# design.net
KiCad netlist of a schematic drawn in EasyEDA
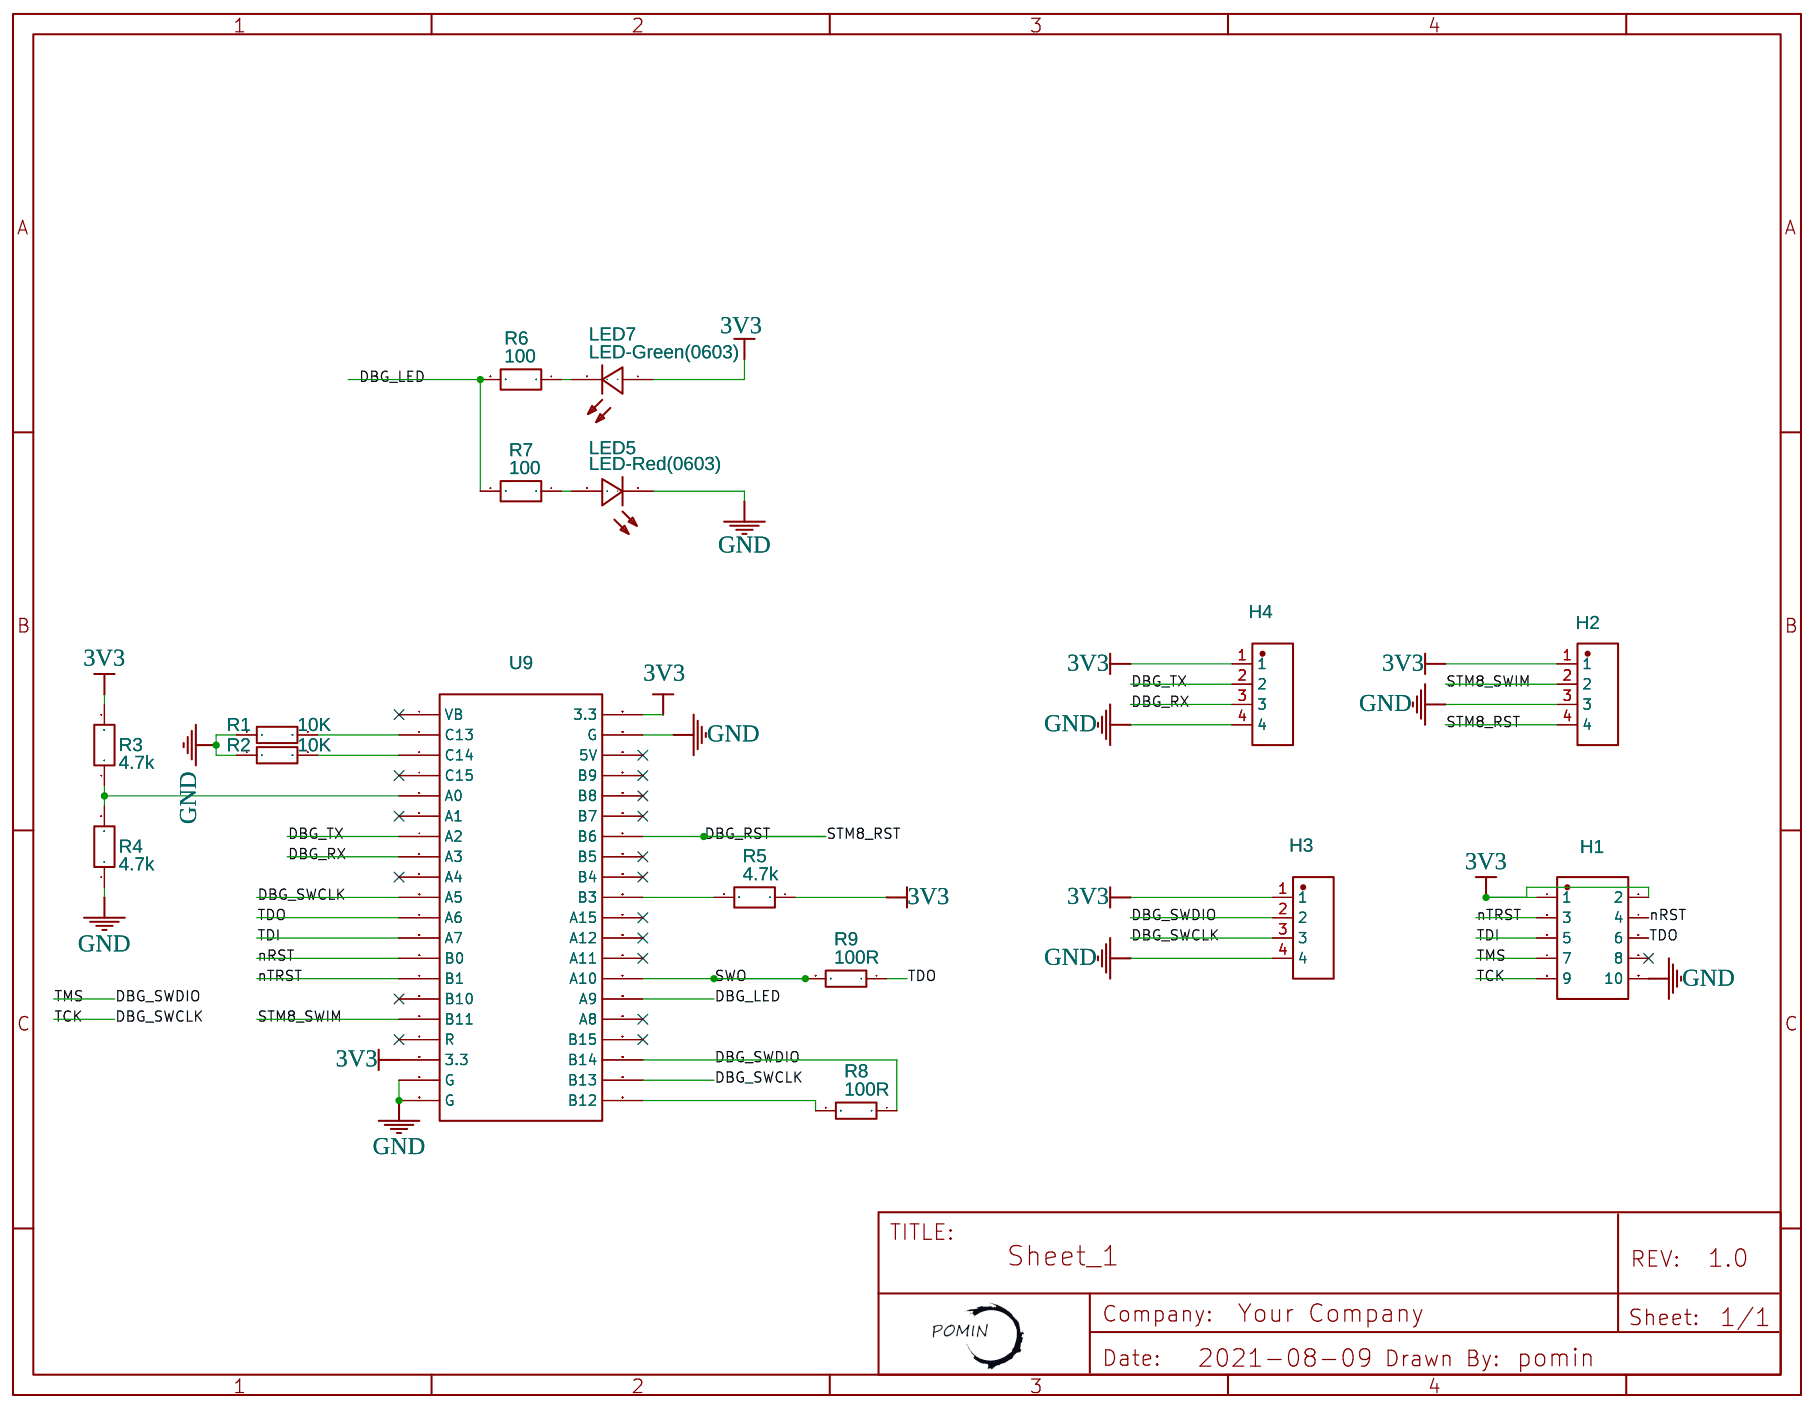
[diagram p0: schematic sheet]

(export (version "E")
  (design (tool "Eeschema 10.0.6"))
  (components
    (comp (ref "H1")
      (value "Female header2.54mm2*5p Straight")
      (fields (field (name "BOM_Supplier Part") "C30419"))
      (libsource (lib "") (part "Female header2.54mm2*5p Straight"))
    )
    (comp (ref "H2")
      (value "2.54-1*4P母")
      (fields (field (name "BOM_Supplier Part") "C2718488"))
      (libsource (lib "") (part "2.54-1*4P母"))
    )
    (comp (ref "H3")
      (value "2.54-1*4P母")
      (fields (field (name "BOM_Supplier Part") "C2718488"))
      (libsource (lib "") (part "2.54-1*4P母"))
    )
    (comp (ref "H4")
      (value "2.54-1*4P母")
      (fields (field (name "BOM_Supplier Part") "C2718488"))
      (libsource (lib "") (part "2.54-1*4P母"))
    )
    (comp (ref "LED5")
      (value "LED-Red(0603)")
      (fields (field (name "BOM_Manufacturer Part") "KT-0603R") (field (name "BOM_Supplier Part") "C2286"))
      (libsource (lib "") (part "Unknown_535_-405"))
    )
    (comp (ref "LED7")
      (value "LED-Green(0603)")
      (fields
        (field (name "BOM_Manufacturer Part") "FC-DA1608UGK-520D10")
        (field (name "BOM_Supplier Part") "C84267")
      )
      (libsource (lib "") (part "Unknown_535_-460"))
    )
    (comp (ref "R1")
      (value "10K")
      (fields
        (field (name "BOM_Manufacturer Part") "AC0603FR-0710KL")
        (field (name "BOM_Supplier Part") "C116677")
      )
      (libsource (lib "") (part "RC0603DR-0710KL"))
    )
    (comp (ref "R2")
      (value "10K")
      (fields
        (field (name "BOM_Manufacturer Part") "AC0603FR-0710KL")
        (field (name "BOM_Supplier Part") "C116677")
      )
      (libsource (lib "") (part "RC0603DR-0710KL"))
    )
    (comp (ref "R3")
      (value "4.7k")
      (fields
        (field (name "BOM_Manufacturer Part") "AC0603FR-074K7L")
        (field (name "BOM_Supplier Part") "C116697")
      )
      (libsource (lib "") (part "Res_0603(1/10W)_EU"))
    )
    (comp (ref "R4")
      (value "4.7k")
      (fields
        (field (name "BOM_Manufacturer Part") "AC0603FR-074K7L")
        (field (name "BOM_Supplier Part") "C116697")
      )
      (libsource (lib "") (part "Res_0603(1/10W)_EU"))
    )
    (comp (ref "R5")
      (value "4.7k")
      (fields
        (field (name "BOM_Manufacturer Part") "AC0603FR-074K7L")
        (field (name "BOM_Supplier Part") "C116697")
      )
      (libsource (lib "") (part "Res_0603(1/10W)_EU_1"))
    )
    (comp (ref "R6")
      (value "100")
      (fields (field (name "BOM_Manufacturer Part") "?"))
      (libsource (lib "") (part "Res_0603(1/10W)_EU_1"))
    )
    (comp (ref "R7")
      (value "100")
      (fields (field (name "BOM_Manufacturer Part") "?"))
      (libsource (lib "") (part "Res_0603(1/10W)_EU_1"))
    )
    (comp (ref "R8")
      (value "100R")
      (fields
        (field (name "BOM_Manufacturer Part") "RC0603FR-07100RL")
        (field (name "BOM_Supplier Part") "C105588")
      )
      (libsource (lib "") (part "AC0603JR-07100RL"))
    )
    (comp (ref "R9")
      (value "100R")
      (fields
        (field (name "BOM_Manufacturer Part") "RC0603FR-07100RL")
        (field (name "BOM_Supplier Part") "C105588")
      )
      (libsource (lib "") (part "AC0603JR-07100RL"))
    )
    (comp (ref "U9") (value "STM32F103C8T6核心板") (libsource (lib "") (part "STM32F103C8T6核心板")))
  )
  (nets
    (net (code "1") (name "/DBG_LED") (class "Default")
      (node (ref "R6") (pin "2") (pinfunction "2_2") (pintype "unspecified"))
      (node (ref "R7") (pin "2") (pinfunction "2_2") (pintype "unspecified"))
      (node (ref "U9") (pin "35") (pinfunction "A9_35") (pintype "unspecified"))
    )
    (net (code "2") (name "/DBG_RST") (class "Default")
      (node (ref "H2") (pin "4") (pinfunction "4_4") (pintype "unspecified"))
      (node (ref "U9") (pin "27") (pinfunction "B6_27") (pintype "unspecified"))
    )
    (net (code "3") (name "/DBG_RX") (class "Default")
      (node (ref "H4") (pin "3") (pinfunction "3_3") (pintype "unspecified"))
      (node (ref "U9") (pin "8") (pinfunction "A3_8") (pintype "unspecified"))
    )
    (net (code "4") (name "/DBG_SWCLK") (class "Default")
      (node (ref "H1") (pin "9") (pinfunction "9_9") (pintype "unspecified"))
      (node (ref "H3") (pin "3") (pinfunction "3_3") (pintype "unspecified"))
      (node (ref "U9") (pin "10") (pinfunction "A5_10") (pintype "unspecified"))
      (node (ref "U9") (pin "39") (pinfunction "B13_39") (pintype "unspecified"))
    )
    (net (code "5") (name "/DBG_SWDIO") (class "Default")
      (node (ref "H1") (pin "7") (pinfunction "7_7") (pintype "unspecified"))
      (node (ref "H3") (pin "2") (pinfunction "2_2") (pintype "unspecified"))
      (node (ref "R8") (pin "1") (pinfunction "1_1") (pintype "unspecified"))
      (node (ref "U9") (pin "38") (pinfunction "B14_38") (pintype "unspecified"))
    )
    (net (code "6") (name "/DBG_TX") (class "Default")
      (node (ref "H4") (pin "2") (pinfunction "2_2") (pintype "unspecified"))
      (node (ref "U9") (pin "7") (pinfunction "A2_7") (pintype "unspecified"))
    )
    (net (code "7") (name "/STM8_SWIM") (class "Default")
      (node (ref "H2") (pin "2") (pinfunction "2_2") (pintype "unspecified"))
      (node (ref "U9") (pin "16") (pinfunction "B11_16") (pintype "unspecified"))
    )
    (net (code "8") (name "/SWO") (class "Default")
      (node (ref "R9") (pin "2") (pinfunction "2_2") (pintype "unspecified"))
      (node (ref "U9") (pin "34") (pinfunction "A10_34") (pintype "unspecified"))
    )
    (net (code "9") (name "/TDI") (class "Default")
      (node (ref "H1") (pin "5") (pinfunction "5_5") (pintype "unspecified"))
      (node (ref "U9") (pin "12") (pinfunction "A7_12") (pintype "unspecified"))
    )
    (net (code "10") (name "/TDO") (class "Default")
      (node (ref "H1") (pin "6") (pinfunction "6_6") (pintype "unspecified"))
      (node (ref "R9") (pin "1") (pinfunction "1_1") (pintype "unspecified"))
      (node (ref "U9") (pin "11") (pinfunction "A6_11") (pintype "unspecified"))
    )
    (net (code "11") (name "/nRST") (class "Default")
      (node (ref "H1") (pin "4") (pinfunction "4_4") (pintype "unspecified"))
      (node (ref "U9") (pin "13") (pinfunction "B0_13") (pintype "unspecified"))
    )
    (net (code "12") (name "/nTRST") (class "Default")
      (node (ref "H1") (pin "3") (pinfunction "3_3") (pintype "unspecified"))
      (node (ref "U9") (pin "14") (pinfunction "B1_14") (pintype "unspecified"))
    )
    (net (code "13") (name "3V3") (class "Default")
      (node (ref "H1") (pin "1") (pinfunction "1_1") (pintype "unspecified"))
      (node (ref "H1") (pin "2") (pinfunction "2_2") (pintype "unspecified"))
      (node (ref "H2") (pin "1") (pinfunction "1_1") (pintype "unspecified"))
      (node (ref "H3") (pin "1") (pinfunction "1_1") (pintype "unspecified"))
      (node (ref "H4") (pin "1") (pinfunction "1_1") (pintype "unspecified"))
      (node (ref "LED7") (pin "1") (pinfunction "+_1") (pintype "unspecified"))
      (node (ref "R3") (pin "2") (pinfunction "2_2") (pintype "unspecified"))
      (node (ref "R5") (pin "1") (pinfunction "1_1") (pintype "unspecified"))
      (node (ref "U9") (pin "18") (pinfunction "3.3_18") (pintype "unspecified"))
      (node (ref "U9") (pin "21") (pinfunction "3.3_21") (pintype "unspecified"))
    )
    (net (code "14") (name "GND") (class "Default")
      (node (ref "H1") (pin "10") (pinfunction "10_10") (pintype "unspecified"))
      (node (ref "H2") (pin "3") (pinfunction "3_3") (pintype "unspecified"))
      (node (ref "H3") (pin "4") (pinfunction "4_4") (pintype "unspecified"))
      (node (ref "H4") (pin "4") (pinfunction "4_4") (pintype "unspecified"))
      (node (ref "LED5") (pin "2") (pinfunction "-_2") (pintype "unspecified"))
      (node (ref "R1") (pin "1") (pinfunction "1_1") (pintype "input"))
      (node (ref "R2") (pin "1") (pinfunction "1_1") (pintype "input"))
      (node (ref "R4") (pin "1") (pinfunction "1_1") (pintype "unspecified"))
      (node (ref "U9") (pin "19") (pinfunction "G_19") (pintype "unspecified"))
      (node (ref "U9") (pin "20") (pinfunction "G_20") (pintype "unspecified"))
      (node (ref "U9") (pin "22") (pinfunction "G_22") (pintype "unspecified"))
    )
    (net (code "15") (name "Net-(LED5-+)") (class "Default")
      (node (ref "LED5") (pin "1") (pinfunction "+_1") (pintype "unspecified"))
      (node (ref "R7") (pin "1") (pinfunction "1_1") (pintype "unspecified"))
    )
    (net (code "16") (name "Net-(LED7--)") (class "Default")
      (node (ref "LED7") (pin "2") (pinfunction "-_2") (pintype "unspecified"))
      (node (ref "R6") (pin "1") (pinfunction "1_1") (pintype "unspecified"))
    )
    (net (code "17") (name "Net-(U9-A0)") (class "Default")
      (node (ref "R3") (pin "1") (pinfunction "1_1") (pintype "unspecified"))
      (node (ref "R4") (pin "2") (pinfunction "2_2") (pintype "unspecified"))
      (node (ref "U9") (pin "5") (pinfunction "A0_5") (pintype "unspecified"))
    )
    (net (code "18") (name "Net-(U9-B3)") (class "Default")
      (node (ref "R5") (pin "2") (pinfunction "2_2") (pintype "unspecified"))
      (node (ref "U9") (pin "30") (pinfunction "B3_30") (pintype "unspecified"))
    )
    (net (code "19") (name "Net-(U9-B12)") (class "Default")
      (node (ref "R8") (pin "2") (pinfunction "2_2") (pintype "unspecified"))
      (node (ref "U9") (pin "40") (pinfunction "B12_40") (pintype "unspecified"))
    )
    (net (code "20") (name "Net-(U9-C13)") (class "Default")
      (node (ref "R1") (pin "2") (pinfunction "2_2") (pintype "input"))
      (node (ref "U9") (pin "2") (pinfunction "C13_2") (pintype "unspecified"))
    )
    (net (code "21") (name "Net-(U9-C14)") (class "Default")
      (node (ref "R2") (pin "2") (pinfunction "2_2") (pintype "input"))
      (node (ref "U9") (pin "3") (pinfunction "C14_3") (pintype "unspecified"))
    )
    (net (code "22") (name "unconnected-(H1-Pad8)") (class "Default")
      (node (ref "H1") (pin "8") (pinfunction "8_8") (pintype "unspecified+no_connect"))
    )
    (net (code "23") (name "unconnected-(U9-5V-Pad23)") (class "Default")
      (node (ref "U9") (pin "23") (pinfunction "5V_23") (pintype "unspecified+no_connect"))
    )
    (net (code "24") (name "unconnected-(U9-A1-Pad6)") (class "Default")
      (node (ref "U9") (pin "6") (pinfunction "A1_6") (pintype "unspecified+no_connect"))
    )
    (net (code "25") (name "unconnected-(U9-A4-Pad9)") (class "Default")
      (node (ref "U9") (pin "9") (pinfunction "A4_9") (pintype "unspecified+no_connect"))
    )
    (net (code "26") (name "unconnected-(U9-A8-Pad36)") (class "Default")
      (node (ref "U9") (pin "36") (pinfunction "A8_36") (pintype "unspecified+no_connect"))
    )
    (net (code "27") (name "unconnected-(U9-A11-Pad33)") (class "Default")
      (node (ref "U9") (pin "33") (pinfunction "A11_33") (pintype "unspecified+no_connect"))
    )
    (net (code "28") (name "unconnected-(U9-A12-Pad32)") (class "Default")
      (node (ref "U9") (pin "32") (pinfunction "A12_32") (pintype "unspecified+no_connect"))
    )
    (net (code "29") (name "unconnected-(U9-A15-Pad31)") (class "Default")
      (node (ref "U9") (pin "31") (pinfunction "A15_31") (pintype "unspecified+no_connect"))
    )
    (net (code "30") (name "unconnected-(U9-B4-Pad29)") (class "Default")
      (node (ref "U9") (pin "29") (pinfunction "B4_29") (pintype "unspecified+no_connect"))
    )
    (net (code "31") (name "unconnected-(U9-B5-Pad28)") (class "Default")
      (node (ref "U9") (pin "28") (pinfunction "B5_28") (pintype "unspecified+no_connect"))
    )
    (net (code "32") (name "unconnected-(U9-B7-Pad26)") (class "Default")
      (node (ref "U9") (pin "26") (pinfunction "B7_26") (pintype "unspecified+no_connect"))
    )
    (net (code "33") (name "unconnected-(U9-B8-Pad25)") (class "Default")
      (node (ref "U9") (pin "25") (pinfunction "B8_25") (pintype "unspecified+no_connect"))
    )
    (net (code "34") (name "unconnected-(U9-B9-Pad24)") (class "Default")
      (node (ref "U9") (pin "24") (pinfunction "B9_24") (pintype "unspecified+no_connect"))
    )
    (net (code "35") (name "unconnected-(U9-B10-Pad15)") (class "Default")
      (node (ref "U9") (pin "15") (pinfunction "B10_15") (pintype "unspecified+no_connect"))
    )
    (net (code "36") (name "unconnected-(U9-B15-Pad37)") (class "Default")
      (node (ref "U9") (pin "37") (pinfunction "B15_37") (pintype "unspecified+no_connect"))
    )
    (net (code "37") (name "unconnected-(U9-C15-Pad4)") (class "Default")
      (node (ref "U9") (pin "4") (pinfunction "C15_4") (pintype "unspecified+no_connect"))
    )
    (net (code "38") (name "unconnected-(U9-R-Pad17)") (class "Default")
      (node (ref "U9") (pin "17") (pinfunction "R_17") (pintype "unspecified+no_connect"))
    )
    (net (code "39") (name "unconnected-(U9-VB-Pad1)") (class "Default")
      (node (ref "U9") (pin "1") (pinfunction "VB_1") (pintype "unspecified+no_connect"))
    )
  )
)
